# mixer-board2.net
KiCad netlist of a schematic drawn in EAGLE
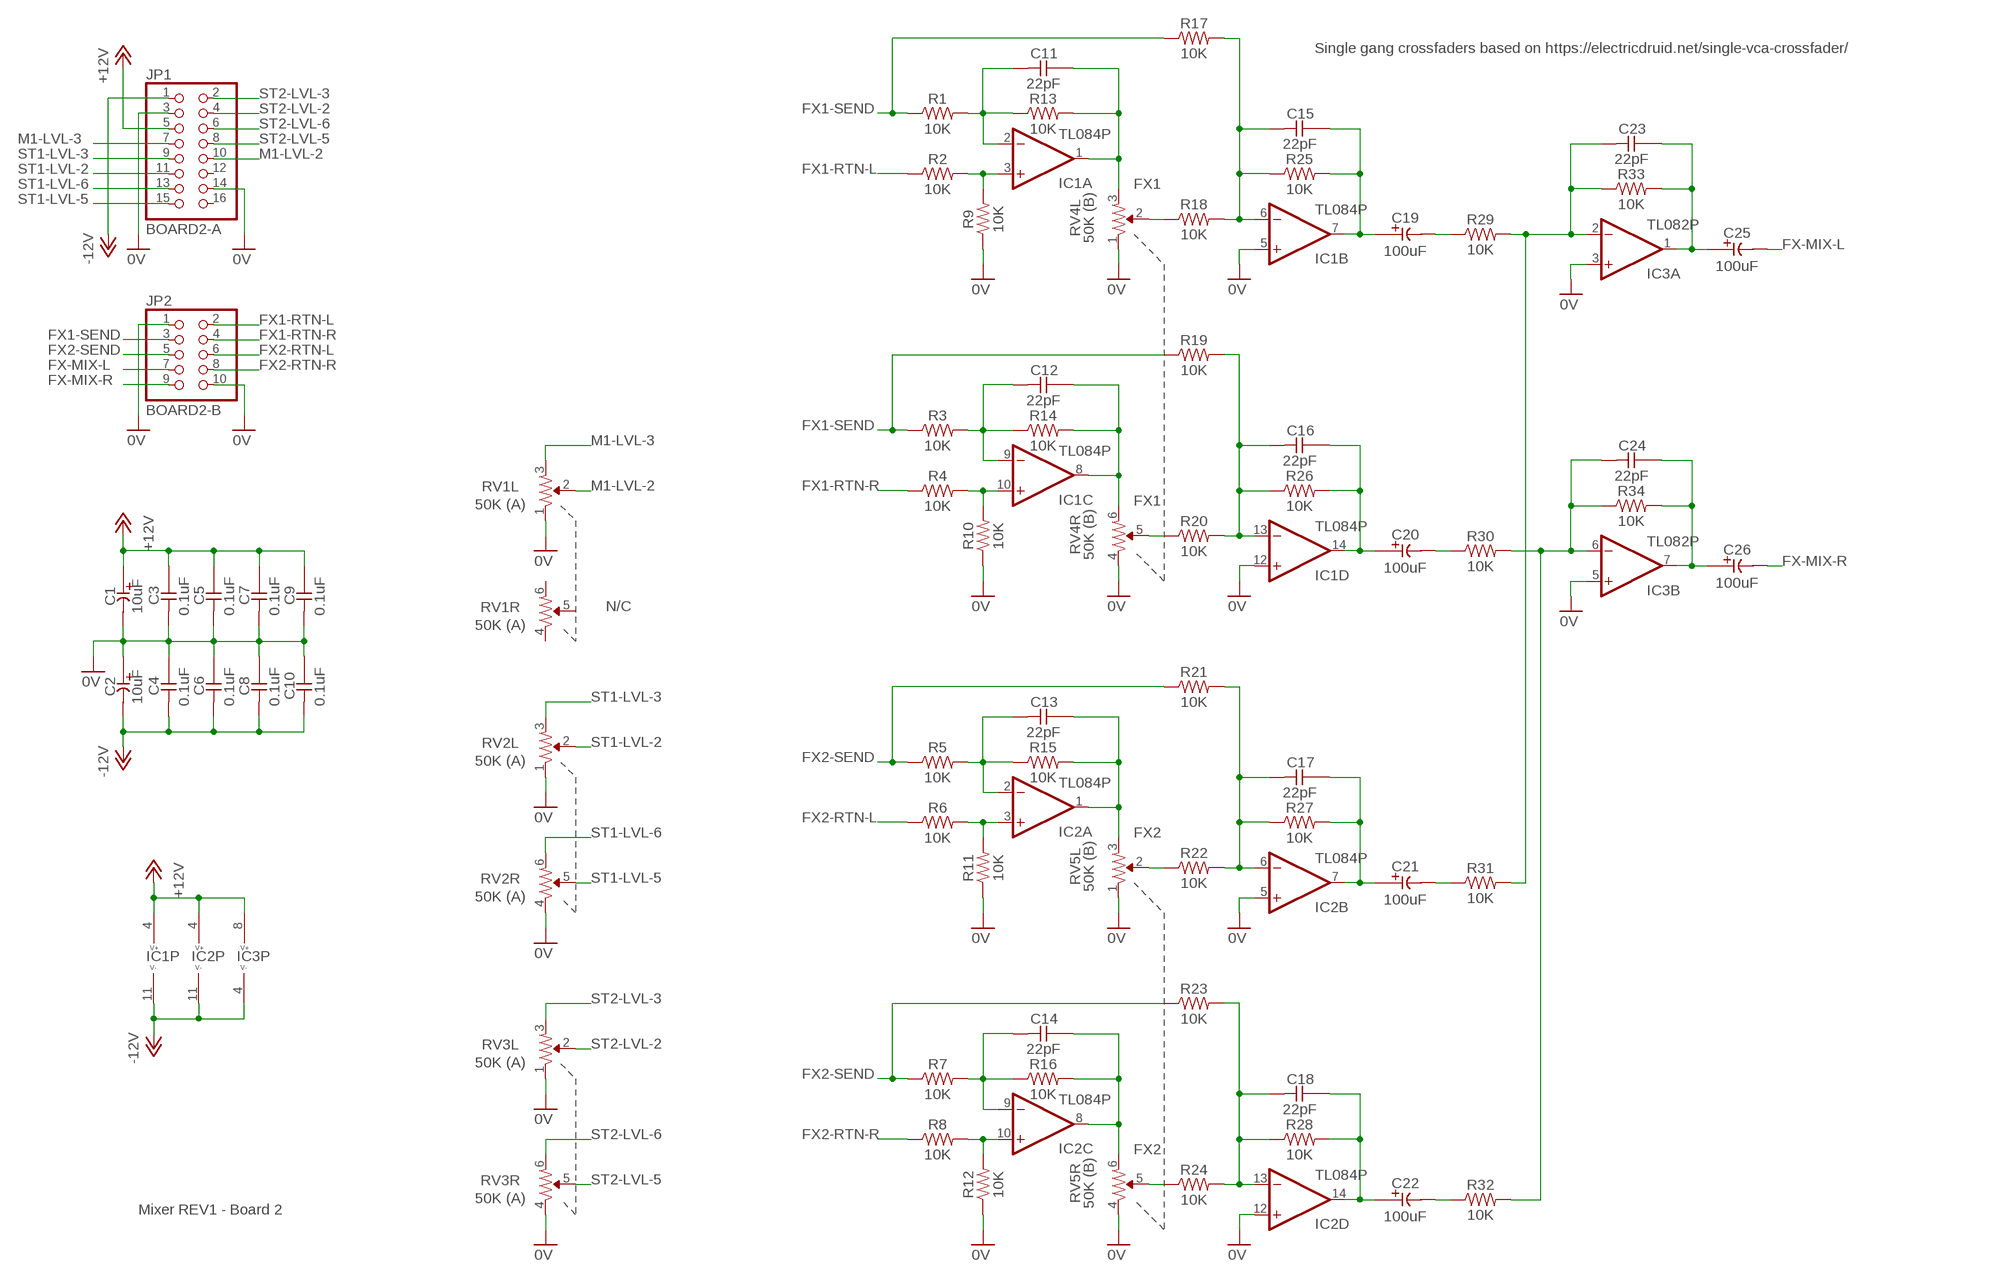
[diagram p0: schematic, sheet 1]

(export (version "E")
  (design (tool "Eeschema 10.0.6"))
  (components
    (comp (ref "C1")
      (value "10uF")
      (footprint "eagle-import:E2-5")
      (libsource (lib "eagle-import") (part "_common.v1_CE-USE2-5"))
    )
    (comp (ref "C2")
      (value "10uF")
      (footprint "eagle-import:E2-5")
      (libsource (lib "eagle-import") (part "_common.v1_CE-USE2-5"))
    )
    (comp (ref "C3")
      (value "0.1uF")
      (footprint "eagle-import:C025-024X044")
      (libsource (lib "eagle-import") (part "_common.v1_CC-US025-024X044"))
    )
    (comp (ref "C4")
      (value "0.1uF")
      (footprint "eagle-import:C025-024X044")
      (libsource (lib "eagle-import") (part "_common.v1_CC-US025-024X044"))
    )
    (comp (ref "C5")
      (value "0.1uF")
      (footprint "eagle-import:C025-024X044")
      (libsource (lib "eagle-import") (part "_common.v1_CC-US025-024X044"))
    )
    (comp (ref "C6")
      (value "0.1uF")
      (footprint "eagle-import:C025-024X044")
      (libsource (lib "eagle-import") (part "_common.v1_CC-US025-024X044"))
    )
    (comp (ref "C7")
      (value "0.1uF")
      (footprint "eagle-import:C025-024X044")
      (libsource (lib "eagle-import") (part "_common.v1_CC-US025-024X044"))
    )
    (comp (ref "C8")
      (value "0.1uF")
      (footprint "eagle-import:C025-024X044")
      (libsource (lib "eagle-import") (part "_common.v1_CC-US025-024X044"))
    )
    (comp (ref "C9")
      (value "0.1uF")
      (footprint "eagle-import:C025-024X044")
      (libsource (lib "eagle-import") (part "_common.v1_CC-US025-024X044"))
    )
    (comp (ref "C10")
      (value "0.1uF")
      (footprint "eagle-import:C025-024X044")
      (libsource (lib "eagle-import") (part "_common.v1_CC-US025-024X044"))
    )
    (comp (ref "C11")
      (value "22pF")
      (footprint "eagle-import:C025-024X044")
      (libsource (lib "eagle-import") (part "CC-US025-024X044"))
    )
    (comp (ref "C12")
      (value "22pF")
      (footprint "eagle-import:C025-024X044")
      (libsource (lib "eagle-import") (part "CC-US025-024X044"))
    )
    (comp (ref "C13")
      (value "22pF")
      (footprint "eagle-import:C025-024X044")
      (libsource (lib "eagle-import") (part "CC-US025-024X044"))
    )
    (comp (ref "C14")
      (value "22pF")
      (footprint "eagle-import:C025-024X044")
      (libsource (lib "eagle-import") (part "CC-US025-024X044"))
    )
    (comp (ref "C15")
      (value "22pF")
      (footprint "eagle-import:C025-024X044")
      (libsource (lib "eagle-import") (part "CC-US025-024X044"))
    )
    (comp (ref "C16")
      (value "22pF")
      (footprint "eagle-import:C025-024X044")
      (libsource (lib "eagle-import") (part "CC-US025-024X044"))
    )
    (comp (ref "C17")
      (value "22pF")
      (footprint "eagle-import:C025-024X044")
      (libsource (lib "eagle-import") (part "CC-US025-024X044"))
    )
    (comp (ref "C18")
      (value "22pF")
      (footprint "eagle-import:C025-024X044")
      (libsource (lib "eagle-import") (part "CC-US025-024X044"))
    )
    (comp (ref "C19")
      (value "100uF")
      (footprint "eagle-import:E5-8,5")
      (libsource (lib "eagle-import") (part "CE-USE5-8.5"))
    )
    (comp (ref "C20")
      (value "100uF")
      (footprint "eagle-import:E5-8,5")
      (libsource (lib "eagle-import") (part "CE-USE5-8.5"))
    )
    (comp (ref "C21")
      (value "100uF")
      (footprint "eagle-import:E5-8,5")
      (libsource (lib "eagle-import") (part "CE-USE5-8.5"))
    )
    (comp (ref "C22")
      (value "100uF")
      (footprint "eagle-import:E5-8,5")
      (libsource (lib "eagle-import") (part "CE-USE5-8.5"))
    )
    (comp (ref "C23")
      (value "22pF")
      (footprint "eagle-import:C025-024X044")
      (libsource (lib "eagle-import") (part "CC-US025-024X044"))
    )
    (comp (ref "C24")
      (value "22pF")
      (footprint "eagle-import:C025-024X044")
      (libsource (lib "eagle-import") (part "CC-US025-024X044"))
    )
    (comp (ref "C25")
      (value "100uF")
      (footprint "eagle-import:E5-8,5")
      (libsource (lib "eagle-import") (part "CE-USE5-8.5"))
    )
    (comp (ref "C26")
      (value "100uF")
      (footprint "eagle-import:E5-8,5")
      (libsource (lib "eagle-import") (part "CE-USE5-8.5"))
    )
    (comp (ref "IC1")
      (value "TL084P")
      (footprint "eagle-import:DIL14")
      (libsource (lib "eagle-import") (part "TL084P"))
    )
    (comp (ref "IC2")
      (value "TL084P")
      (footprint "eagle-import:DIL14")
      (libsource (lib "eagle-import") (part "TL084P"))
    )
    (comp (ref "IC3")
      (value "TL082P")
      (footprint "eagle-import:DIL08")
      (libsource (lib "eagle-import") (part "TL082P"))
    )
    (comp (ref "JP1")
      (value "BOARD2-A")
      (footprint "eagle-import:2X08")
      (libsource (lib "eagle-import") (part "PINHD-2X8"))
    )
    (comp (ref "JP2")
      (value "BOARD2-B")
      (footprint "eagle-import:2X05")
      (libsource (lib "eagle-import") (part "PINHD-2X5"))
    )
    (comp (ref "R1")
      (value "10K")
      (footprint "eagle-import:0207_7")
      (libsource (lib "eagle-import") (part "R"))
    )
    (comp (ref "R2")
      (value "10K")
      (footprint "eagle-import:0207_7")
      (libsource (lib "eagle-import") (part "R"))
    )
    (comp (ref "R3")
      (value "10K")
      (footprint "eagle-import:0207_7")
      (libsource (lib "eagle-import") (part "R"))
    )
    (comp (ref "R4")
      (value "10K")
      (footprint "eagle-import:0207_7")
      (libsource (lib "eagle-import") (part "R"))
    )
    (comp (ref "R5")
      (value "10K")
      (footprint "eagle-import:0207_7")
      (libsource (lib "eagle-import") (part "R"))
    )
    (comp (ref "R6")
      (value "10K")
      (footprint "eagle-import:0207_7")
      (libsource (lib "eagle-import") (part "R"))
    )
    (comp (ref "R7")
      (value "10K")
      (footprint "eagle-import:0207_7")
      (libsource (lib "eagle-import") (part "R"))
    )
    (comp (ref "R8")
      (value "10K")
      (footprint "eagle-import:0207_7")
      (libsource (lib "eagle-import") (part "R"))
    )
    (comp (ref "R9")
      (value "10K")
      (footprint "eagle-import:0207_7")
      (libsource (lib "eagle-import") (part "R"))
    )
    (comp (ref "R10")
      (value "10K")
      (footprint "eagle-import:0207_7")
      (libsource (lib "eagle-import") (part "R"))
    )
    (comp (ref "R11")
      (value "10K")
      (footprint "eagle-import:0207_7")
      (libsource (lib "eagle-import") (part "R"))
    )
    (comp (ref "R12")
      (value "10K")
      (footprint "eagle-import:0207_7")
      (libsource (lib "eagle-import") (part "R"))
    )
    (comp (ref "R13")
      (value "10K")
      (footprint "eagle-import:0207_7")
      (libsource (lib "eagle-import") (part "R"))
    )
    (comp (ref "R14")
      (value "10K")
      (footprint "eagle-import:0207_7")
      (libsource (lib "eagle-import") (part "R"))
    )
    (comp (ref "R15")
      (value "10K")
      (footprint "eagle-import:0207_7")
      (libsource (lib "eagle-import") (part "R"))
    )
    (comp (ref "R16")
      (value "10K")
      (footprint "eagle-import:0207_7")
      (libsource (lib "eagle-import") (part "R"))
    )
    (comp (ref "R17")
      (value "10K")
      (footprint "eagle-import:0207_7")
      (libsource (lib "eagle-import") (part "R"))
    )
    (comp (ref "R18")
      (value "10K")
      (footprint "eagle-import:0207_7")
      (libsource (lib "eagle-import") (part "R"))
    )
    (comp (ref "R19")
      (value "10K")
      (footprint "eagle-import:0207_7")
      (libsource (lib "eagle-import") (part "R"))
    )
    (comp (ref "R20")
      (value "10K")
      (footprint "eagle-import:0207_7")
      (libsource (lib "eagle-import") (part "R"))
    )
    (comp (ref "R21")
      (value "10K")
      (footprint "eagle-import:0207_7")
      (libsource (lib "eagle-import") (part "R"))
    )
    (comp (ref "R22")
      (value "10K")
      (footprint "eagle-import:0207_7")
      (libsource (lib "eagle-import") (part "R"))
    )
    (comp (ref "R23")
      (value "10K")
      (footprint "eagle-import:0207_7")
      (libsource (lib "eagle-import") (part "R"))
    )
    (comp (ref "R24")
      (value "10K")
      (footprint "eagle-import:0207_7")
      (libsource (lib "eagle-import") (part "R"))
    )
    (comp (ref "R25")
      (value "10K")
      (footprint "eagle-import:0207_7")
      (libsource (lib "eagle-import") (part "R"))
    )
    (comp (ref "R26")
      (value "10K")
      (footprint "eagle-import:0207_7")
      (libsource (lib "eagle-import") (part "R"))
    )
    (comp (ref "R27")
      (value "10K")
      (footprint "eagle-import:0207_7")
      (libsource (lib "eagle-import") (part "R"))
    )
    (comp (ref "R28")
      (value "10K")
      (footprint "eagle-import:0207_7")
      (libsource (lib "eagle-import") (part "R"))
    )
    (comp (ref "R29")
      (value "10K")
      (footprint "eagle-import:0207_7")
      (libsource (lib "eagle-import") (part "R"))
    )
    (comp (ref "R30")
      (value "10K")
      (footprint "eagle-import:0207_7")
      (libsource (lib "eagle-import") (part "R"))
    )
    (comp (ref "R31")
      (value "10K")
      (footprint "eagle-import:0207_7")
      (libsource (lib "eagle-import") (part "R"))
    )
    (comp (ref "R32")
      (value "10K")
      (footprint "eagle-import:0207_7")
      (libsource (lib "eagle-import") (part "R"))
    )
    (comp (ref "R33")
      (value "10K")
      (footprint "eagle-import:0207_7")
      (libsource (lib "eagle-import") (part "R"))
    )
    (comp (ref "R34")
      (value "10K")
      (footprint "eagle-import:0207_7")
      (libsource (lib "eagle-import") (part "R"))
    )
    (comp (ref "RV1")
      (value "50K (A)")
      (footprint "eagle-import:_COMMON_3RP_1610G")
      (libsource (lib "eagle-import") (part "R-VAR-ST"))
    )
    (comp (ref "RV2")
      (value "50K (A)")
      (footprint "eagle-import:_COMMON_3RP_1610G")
      (libsource (lib "eagle-import") (part "R-VAR-ST"))
    )
    (comp (ref "RV3")
      (value "50K (A)")
      (footprint "eagle-import:_COMMON_3RP_1610G")
      (libsource (lib "eagle-import") (part "R-VAR-ST"))
    )
    (comp (ref "RV4")
      (value "50K (B)")
      (footprint "eagle-import:_COMMON_3RP_1610G")
      (libsource (lib "eagle-import") (part "R-VAR-ST"))
    )
    (comp (ref "RV5")
      (value "50K (B)")
      (footprint "eagle-import:_COMMON_3RP_1610G")
      (libsource (lib "eagle-import") (part "R-VAR-ST"))
    )
  )
  (nets
    (net (code "1") (name "+12V") (class "Default")
      (node (ref "C1") (pin "+") (pinfunction "+_+") (pintype "passive"))
      (node (ref "C3") (pin "1") (pinfunction "1_1") (pintype "passive"))
      (node (ref "C5") (pin "1") (pinfunction "1_1") (pintype "passive"))
      (node (ref "C7") (pin "1") (pinfunction "1_1") (pintype "passive"))
      (node (ref "C9") (pin "1") (pinfunction "1_1") (pintype "passive"))
      (node (ref "IC1") (pin "4") (pinfunction "V+_4") (pintype "power_in"))
      (node (ref "IC2") (pin "4") (pinfunction "V+_4") (pintype "power_in"))
      (node (ref "IC3") (pin "8") (pinfunction "V+_8") (pintype "power_in"))
      (node (ref "JP1") (pin "5") (pinfunction "5_5") (pintype "passive"))
    )
    (net (code "2") (name "-12V") (class "Default")
      (node (ref "C10") (pin "2") (pinfunction "2_2") (pintype "passive"))
      (node (ref "C2") (pin "-") (pinfunction "-_-") (pintype "passive"))
      (node (ref "C4") (pin "2") (pinfunction "2_2") (pintype "passive"))
      (node (ref "C6") (pin "2") (pinfunction "2_2") (pintype "passive"))
      (node (ref "C8") (pin "2") (pinfunction "2_2") (pintype "passive"))
      (node (ref "IC1") (pin "11") (pinfunction "V-_11") (pintype "power_in"))
      (node (ref "IC2") (pin "11") (pinfunction "V-_11") (pintype "power_in"))
      (node (ref "IC3") (pin "4") (pinfunction "V-_4") (pintype "power_in"))
      (node (ref "JP1") (pin "1") (pinfunction "1_1") (pintype "passive"))
    )
    (net (code "3") (name "/FX-MIX-L") (class "Default")
      (node (ref "C25") (pin "-") (pinfunction "-_-") (pintype "passive"))
      (node (ref "JP2") (pin "7") (pinfunction "7_7") (pintype "passive"))
    )
    (net (code "4") (name "/FX-MIX-R") (class "Default")
      (node (ref "C26") (pin "-") (pinfunction "-_-") (pintype "passive"))
      (node (ref "JP2") (pin "9") (pinfunction "9_9") (pintype "passive"))
    )
    (net (code "5") (name "/FX1-RTN-L") (class "Default")
      (node (ref "JP2") (pin "2") (pinfunction "2_2") (pintype "passive"))
      (node (ref "R2") (pin "1") (pinfunction "1_1") (pintype "passive"))
    )
    (net (code "6") (name "/FX1-RTN-R") (class "Default")
      (node (ref "JP2") (pin "4") (pinfunction "4_4") (pintype "passive"))
      (node (ref "R4") (pin "1") (pinfunction "1_1") (pintype "passive"))
    )
    (net (code "7") (name "/FX1-SEND") (class "Default")
      (node (ref "JP2") (pin "3") (pinfunction "3_3") (pintype "passive"))
      (node (ref "R1") (pin "1") (pinfunction "1_1") (pintype "passive"))
      (node (ref "R17") (pin "1") (pinfunction "1_1") (pintype "passive"))
      (node (ref "R19") (pin "1") (pinfunction "1_1") (pintype "passive"))
      (node (ref "R3") (pin "1") (pinfunction "1_1") (pintype "passive"))
    )
    (net (code "8") (name "/FX2-RTN-L") (class "Default")
      (node (ref "JP2") (pin "6") (pinfunction "6_6") (pintype "passive"))
      (node (ref "R6") (pin "1") (pinfunction "1_1") (pintype "passive"))
    )
    (net (code "9") (name "/FX2-RTN-R") (class "Default")
      (node (ref "JP2") (pin "8") (pinfunction "8_8") (pintype "passive"))
      (node (ref "R8") (pin "1") (pinfunction "1_1") (pintype "passive"))
    )
    (net (code "10") (name "/FX2-SEND") (class "Default")
      (node (ref "JP2") (pin "5") (pinfunction "5_5") (pintype "passive"))
      (node (ref "R21") (pin "1") (pinfunction "1_1") (pintype "passive"))
      (node (ref "R23") (pin "1") (pinfunction "1_1") (pintype "passive"))
      (node (ref "R5") (pin "1") (pinfunction "1_1") (pintype "passive"))
      (node (ref "R7") (pin "1") (pinfunction "1_1") (pintype "passive"))
    )
    (net (code "11") (name "/M1-LVL-2") (class "Default")
      (node (ref "JP1") (pin "10") (pinfunction "10_10") (pintype "passive"))
      (node (ref "RV1") (pin "2") (pinfunction "2_2") (pintype "passive"))
    )
    (net (code "12") (name "/M1-LVL-3") (class "Default")
      (node (ref "JP1") (pin "7") (pinfunction "7_7") (pintype "passive"))
      (node (ref "RV1") (pin "3") (pinfunction "3_3") (pintype "passive"))
    )
    (net (code "13") (name "/ST1-LVL-2") (class "Default")
      (node (ref "JP1") (pin "11") (pinfunction "11_11") (pintype "passive"))
      (node (ref "RV2") (pin "2") (pinfunction "2_2") (pintype "passive"))
    )
    (net (code "14") (name "/ST1-LVL-3") (class "Default")
      (node (ref "JP1") (pin "9") (pinfunction "9_9") (pintype "passive"))
      (node (ref "RV2") (pin "3") (pinfunction "3_3") (pintype "passive"))
    )
    (net (code "15") (name "/ST1-LVL-5") (class "Default")
      (node (ref "JP1") (pin "15") (pinfunction "15_15") (pintype "passive"))
      (node (ref "RV2") (pin "5") (pinfunction "2_5") (pintype "passive"))
    )
    (net (code "16") (name "/ST1-LVL-6") (class "Default")
      (node (ref "JP1") (pin "13") (pinfunction "13_13") (pintype "passive"))
      (node (ref "RV2") (pin "6") (pinfunction "3_6") (pintype "passive"))
    )
    (net (code "17") (name "/ST2-LVL-2") (class "Default")
      (node (ref "JP1") (pin "4") (pinfunction "4_4") (pintype "passive"))
      (node (ref "RV3") (pin "2") (pinfunction "2_2") (pintype "passive"))
    )
    (net (code "18") (name "/ST2-LVL-3") (class "Default")
      (node (ref "JP1") (pin "2") (pinfunction "2_2") (pintype "passive"))
      (node (ref "RV3") (pin "3") (pinfunction "3_3") (pintype "passive"))
    )
    (net (code "19") (name "/ST2-LVL-5") (class "Default")
      (node (ref "JP1") (pin "8") (pinfunction "8_8") (pintype "passive"))
      (node (ref "RV3") (pin "5") (pinfunction "2_5") (pintype "passive"))
    )
    (net (code "20") (name "/ST2-LVL-6") (class "Default")
      (node (ref "JP1") (pin "6") (pinfunction "6_6") (pintype "passive"))
      (node (ref "RV3") (pin "6") (pinfunction "3_6") (pintype "passive"))
    )
    (net (code "21") (name "0V") (class "Default")
      (node (ref "C1") (pin "-") (pinfunction "-_-") (pintype "passive"))
      (node (ref "C10") (pin "1") (pinfunction "1_1") (pintype "passive"))
      (node (ref "C2") (pin "+") (pinfunction "+_+") (pintype "passive"))
      (node (ref "C3") (pin "2") (pinfunction "2_2") (pintype "passive"))
      (node (ref "C4") (pin "1") (pinfunction "1_1") (pintype "passive"))
      (node (ref "C5") (pin "2") (pinfunction "2_2") (pintype "passive"))
      (node (ref "C6") (pin "1") (pinfunction "1_1") (pintype "passive"))
      (node (ref "C7") (pin "2") (pinfunction "2_2") (pintype "passive"))
      (node (ref "C8") (pin "1") (pinfunction "1_1") (pintype "passive"))
      (node (ref "C9") (pin "2") (pinfunction "2_2") (pintype "passive"))
      (node (ref "IC1") (pin "12") (pinfunction "+IN_12") (pintype "input"))
      (node (ref "IC1") (pin "5") (pinfunction "+IN_5") (pintype "input"))
      (node (ref "IC2") (pin "12") (pinfunction "+IN_12") (pintype "input"))
      (node (ref "IC2") (pin "5") (pinfunction "+IN_5") (pintype "input"))
      (node (ref "IC3") (pin "3") (pinfunction "+IN_3") (pintype "input"))
      (node (ref "IC3") (pin "5") (pinfunction "+IN_5") (pintype "input"))
      (node (ref "JP1") (pin "14") (pinfunction "14_14") (pintype "passive"))
      (node (ref "JP1") (pin "3") (pinfunction "3_3") (pintype "passive"))
      (node (ref "JP2") (pin "1") (pinfunction "1_1") (pintype "passive"))
      (node (ref "JP2") (pin "10") (pinfunction "10_10") (pintype "passive"))
      (node (ref "R10") (pin "1") (pinfunction "1_1") (pintype "passive"))
      (node (ref "R11") (pin "1") (pinfunction "1_1") (pintype "passive"))
      (node (ref "R12") (pin "1") (pinfunction "1_1") (pintype "passive"))
      (node (ref "R9") (pin "1") (pinfunction "1_1") (pintype "passive"))
      (node (ref "RV1") (pin "1") (pinfunction "1_1") (pintype "passive"))
      (node (ref "RV2") (pin "1") (pinfunction "1_1") (pintype "passive"))
      (node (ref "RV2") (pin "4") (pinfunction "1_4") (pintype "passive"))
      (node (ref "RV3") (pin "1") (pinfunction "1_1") (pintype "passive"))
      (node (ref "RV3") (pin "4") (pinfunction "1_4") (pintype "passive"))
      (node (ref "RV4") (pin "1") (pinfunction "1_1") (pintype "passive"))
      (node (ref "RV4") (pin "4") (pinfunction "1_4") (pintype "passive"))
      (node (ref "RV5") (pin "1") (pinfunction "1_1") (pintype "passive"))
      (node (ref "RV5") (pin "4") (pinfunction "1_4") (pintype "passive"))
    )
    (net (code "22") (name "Net-(C19-Pad-)") (class "Default")
      (node (ref "C19") (pin "-") (pinfunction "-_-") (pintype "passive"))
      (node (ref "R29") (pin "1") (pinfunction "1_1") (pintype "passive"))
    )
    (net (code "23") (name "Net-(C20-Pad-)") (class "Default")
      (node (ref "C20") (pin "-") (pinfunction "-_-") (pintype "passive"))
      (node (ref "R30") (pin "1") (pinfunction "1_1") (pintype "passive"))
    )
    (net (code "24") (name "Net-(C21-Pad-)") (class "Default")
      (node (ref "C21") (pin "-") (pinfunction "-_-") (pintype "passive"))
      (node (ref "R31") (pin "1") (pinfunction "1_1") (pintype "passive"))
    )
    (net (code "25") (name "Net-(C22-Pad-)") (class "Default")
      (node (ref "C22") (pin "-") (pinfunction "-_-") (pintype "passive"))
      (node (ref "R32") (pin "1") (pinfunction "1_1") (pintype "passive"))
    )
    (net (code "26") (name "Net-(IC1A-+IN)") (class "Default")
      (node (ref "IC1") (pin "3") (pinfunction "+IN_3") (pintype "input"))
      (node (ref "R2") (pin "2") (pinfunction "2_2") (pintype "passive"))
      (node (ref "R9") (pin "2") (pinfunction "2_2") (pintype "passive"))
    )
    (net (code "27") (name "Net-(IC1A--IN)") (class "Default")
      (node (ref "C11") (pin "2") (pinfunction "2_2") (pintype "passive"))
      (node (ref "IC1") (pin "2") (pinfunction "-IN_2") (pintype "input"))
      (node (ref "R1") (pin "2") (pinfunction "2_2") (pintype "passive"))
      (node (ref "R13") (pin "1") (pinfunction "1_1") (pintype "passive"))
    )
    (net (code "28") (name "Net-(IC1A-OUT)") (class "Default")
      (node (ref "C11") (pin "1") (pinfunction "1_1") (pintype "passive"))
      (node (ref "IC1") (pin "1") (pinfunction "OUT_1") (pintype "output"))
      (node (ref "R13") (pin "2") (pinfunction "2_2") (pintype "passive"))
      (node (ref "RV4") (pin "3") (pinfunction "3_3") (pintype "passive"))
    )
    (net (code "29") (name "Net-(IC1B--IN)") (class "Default")
      (node (ref "C15") (pin "2") (pinfunction "2_2") (pintype "passive"))
      (node (ref "IC1") (pin "6") (pinfunction "-IN_6") (pintype "input"))
      (node (ref "R17") (pin "2") (pinfunction "2_2") (pintype "passive"))
      (node (ref "R18") (pin "2") (pinfunction "2_2") (pintype "passive"))
      (node (ref "R25") (pin "1") (pinfunction "1_1") (pintype "passive"))
    )
    (net (code "30") (name "Net-(IC1B-OUT)") (class "Default")
      (node (ref "C15") (pin "1") (pinfunction "1_1") (pintype "passive"))
      (node (ref "C19") (pin "+") (pinfunction "+_+") (pintype "passive"))
      (node (ref "IC1") (pin "7") (pinfunction "OUT_7") (pintype "output"))
      (node (ref "R25") (pin "2") (pinfunction "2_2") (pintype "passive"))
    )
    (net (code "31") (name "Net-(IC1C-+IN)") (class "Default")
      (node (ref "IC1") (pin "10") (pinfunction "+IN_10") (pintype "input"))
      (node (ref "R10") (pin "2") (pinfunction "2_2") (pintype "passive"))
      (node (ref "R4") (pin "2") (pinfunction "2_2") (pintype "passive"))
    )
    (net (code "32") (name "Net-(IC1C--IN)") (class "Default")
      (node (ref "C12") (pin "2") (pinfunction "2_2") (pintype "passive"))
      (node (ref "IC1") (pin "9") (pinfunction "-IN_9") (pintype "input"))
      (node (ref "R14") (pin "1") (pinfunction "1_1") (pintype "passive"))
      (node (ref "R3") (pin "2") (pinfunction "2_2") (pintype "passive"))
    )
    (net (code "33") (name "Net-(IC1C-OUT)") (class "Default")
      (node (ref "C12") (pin "1") (pinfunction "1_1") (pintype "passive"))
      (node (ref "IC1") (pin "8") (pinfunction "OUT_8") (pintype "output"))
      (node (ref "R14") (pin "2") (pinfunction "2_2") (pintype "passive"))
      (node (ref "RV4") (pin "6") (pinfunction "3_6") (pintype "passive"))
    )
    (net (code "34") (name "Net-(IC1D--IN)") (class "Default")
      (node (ref "C16") (pin "2") (pinfunction "2_2") (pintype "passive"))
      (node (ref "IC1") (pin "13") (pinfunction "-IN_13") (pintype "input"))
      (node (ref "R19") (pin "2") (pinfunction "2_2") (pintype "passive"))
      (node (ref "R20") (pin "2") (pinfunction "2_2") (pintype "passive"))
      (node (ref "R26") (pin "1") (pinfunction "1_1") (pintype "passive"))
    )
    (net (code "35") (name "Net-(IC1D-OUT)") (class "Default")
      (node (ref "C16") (pin "1") (pinfunction "1_1") (pintype "passive"))
      (node (ref "C20") (pin "+") (pinfunction "+_+") (pintype "passive"))
      (node (ref "IC1") (pin "14") (pinfunction "OUT_14") (pintype "output"))
      (node (ref "R26") (pin "2") (pinfunction "2_2") (pintype "passive"))
    )
    (net (code "36") (name "Net-(IC2A-+IN)") (class "Default")
      (node (ref "IC2") (pin "3") (pinfunction "+IN_3") (pintype "input"))
      (node (ref "R11") (pin "2") (pinfunction "2_2") (pintype "passive"))
      (node (ref "R6") (pin "2") (pinfunction "2_2") (pintype "passive"))
    )
    (net (code "37") (name "Net-(IC2A--IN)") (class "Default")
      (node (ref "C13") (pin "2") (pinfunction "2_2") (pintype "passive"))
      (node (ref "IC2") (pin "2") (pinfunction "-IN_2") (pintype "input"))
      (node (ref "R15") (pin "1") (pinfunction "1_1") (pintype "passive"))
      (node (ref "R5") (pin "2") (pinfunction "2_2") (pintype "passive"))
    )
    (net (code "38") (name "Net-(IC2A-OUT)") (class "Default")
      (node (ref "C13") (pin "1") (pinfunction "1_1") (pintype "passive"))
      (node (ref "IC2") (pin "1") (pinfunction "OUT_1") (pintype "output"))
      (node (ref "R15") (pin "2") (pinfunction "2_2") (pintype "passive"))
      (node (ref "RV5") (pin "3") (pinfunction "3_3") (pintype "passive"))
    )
    (net (code "39") (name "Net-(IC2B--IN)") (class "Default")
      (node (ref "C17") (pin "2") (pinfunction "2_2") (pintype "passive"))
      (node (ref "IC2") (pin "6") (pinfunction "-IN_6") (pintype "input"))
      (node (ref "R21") (pin "2") (pinfunction "2_2") (pintype "passive"))
      (node (ref "R22") (pin "2") (pinfunction "2_2") (pintype "passive"))
      (node (ref "R27") (pin "1") (pinfunction "1_1") (pintype "passive"))
    )
    (net (code "40") (name "Net-(IC2B-OUT)") (class "Default")
      (node (ref "C17") (pin "1") (pinfunction "1_1") (pintype "passive"))
      (node (ref "C21") (pin "+") (pinfunction "+_+") (pintype "passive"))
      (node (ref "IC2") (pin "7") (pinfunction "OUT_7") (pintype "output"))
      (node (ref "R27") (pin "2") (pinfunction "2_2") (pintype "passive"))
    )
    (net (code "41") (name "Net-(IC2C-+IN)") (class "Default")
      (node (ref "IC2") (pin "10") (pinfunction "+IN_10") (pintype "input"))
      (node (ref "R12") (pin "2") (pinfunction "2_2") (pintype "passive"))
      (node (ref "R8") (pin "2") (pinfunction "2_2") (pintype "passive"))
    )
    (net (code "42") (name "Net-(IC2C--IN)") (class "Default")
      (node (ref "C14") (pin "2") (pinfunction "2_2") (pintype "passive"))
      (node (ref "IC2") (pin "9") (pinfunction "-IN_9") (pintype "input"))
      (node (ref "R16") (pin "1") (pinfunction "1_1") (pintype "passive"))
      (node (ref "R7") (pin "2") (pinfunction "2_2") (pintype "passive"))
    )
    (net (code "43") (name "Net-(IC2C-OUT)") (class "Default")
      (node (ref "C14") (pin "1") (pinfunction "1_1") (pintype "passive"))
      (node (ref "IC2") (pin "8") (pinfunction "OUT_8") (pintype "output"))
      (node (ref "R16") (pin "2") (pinfunction "2_2") (pintype "passive"))
      (node (ref "RV5") (pin "6") (pinfunction "3_6") (pintype "passive"))
    )
    (net (code "44") (name "Net-(IC2D--IN)") (class "Default")
      (node (ref "C18") (pin "2") (pinfunction "2_2") (pintype "passive"))
      (node (ref "IC2") (pin "13") (pinfunction "-IN_13") (pintype "input"))
      (node (ref "R23") (pin "2") (pinfunction "2_2") (pintype "passive"))
      (node (ref "R24") (pin "2") (pinfunction "2_2") (pintype "passive"))
      (node (ref "R28") (pin "1") (pinfunction "1_1") (pintype "passive"))
    )
    (net (code "45") (name "Net-(IC2D-OUT)") (class "Default")
      (node (ref "C18") (pin "1") (pinfunction "1_1") (pintype "passive"))
      (node (ref "C22") (pin "+") (pinfunction "+_+") (pintype "passive"))
      (node (ref "IC2") (pin "14") (pinfunction "OUT_14") (pintype "output"))
      (node (ref "R28") (pin "2") (pinfunction "2_2") (pintype "passive"))
    )
    (net (code "46") (name "Net-(IC3A--IN)") (class "Default")
      (node (ref "C23") (pin "2") (pinfunction "2_2") (pintype "passive"))
      (node (ref "IC3") (pin "2") (pinfunction "-IN_2") (pintype "input"))
      (node (ref "R29") (pin "2") (pinfunction "2_2") (pintype "passive"))
      (node (ref "R31") (pin "2") (pinfunction "2_2") (pintype "passive"))
      (node (ref "R33") (pin "1") (pinfunction "1_1") (pintype "passive"))
    )
    (net (code "47") (name "Net-(IC3A-OUT)") (class "Default")
      (node (ref "C23") (pin "1") (pinfunction "1_1") (pintype "passive"))
      (node (ref "C25") (pin "+") (pinfunction "+_+") (pintype "passive"))
      (node (ref "IC3") (pin "1") (pinfunction "OUT_1") (pintype "output"))
      (node (ref "R33") (pin "2") (pinfunction "2_2") (pintype "passive"))
    )
    (net (code "48") (name "Net-(IC3B--IN)") (class "Default")
      (node (ref "C24") (pin "2") (pinfunction "2_2") (pintype "passive"))
      (node (ref "IC3") (pin "6") (pinfunction "-IN_6") (pintype "input"))
      (node (ref "R30") (pin "2") (pinfunction "2_2") (pintype "passive"))
      (node (ref "R32") (pin "2") (pinfunction "2_2") (pintype "passive"))
      (node (ref "R34") (pin "1") (pinfunction "1_1") (pintype "passive"))
    )
    (net (code "49") (name "Net-(IC3B-OUT)") (class "Default")
      (node (ref "C24") (pin "1") (pinfunction "1_1") (pintype "passive"))
      (node (ref "C26") (pin "+") (pinfunction "+_+") (pintype "passive"))
      (node (ref "IC3") (pin "7") (pinfunction "OUT_7") (pintype "output"))
      (node (ref "R34") (pin "2") (pinfunction "2_2") (pintype "passive"))
    )
    (net (code "50") (name "Net-(R18-Pad1)") (class "Default")
      (node (ref "R18") (pin "1") (pinfunction "1_1") (pintype "passive"))
      (node (ref "RV4") (pin "2") (pinfunction "2_2") (pintype "passive"))
    )
    (net (code "51") (name "Net-(R22-Pad1)") (class "Default")
      (node (ref "R22") (pin "1") (pinfunction "1_1") (pintype "passive"))
      (node (ref "RV5") (pin "2") (pinfunction "2_2") (pintype "passive"))
    )
    (net (code "52") (name "Net-(RV4B-2)") (class "Default")
      (node (ref "R20") (pin "1") (pinfunction "1_1") (pintype "passive"))
      (node (ref "RV4") (pin "5") (pinfunction "2_5") (pintype "passive"))
    )
    (net (code "53") (name "Net-(RV5B-2)") (class "Default")
      (node (ref "R24") (pin "1") (pinfunction "1_1") (pintype "passive"))
      (node (ref "RV5") (pin "5") (pinfunction "2_5") (pintype "passive"))
    )
    (net (code "54") (name "unconnected-(JP1-Pad12)") (class "Default")
      (node (ref "JP1") (pin "12") (pinfunction "12_12") (pintype "passive"))
    )
    (net (code "55") (name "unconnected-(JP1-Pad16)") (class "Default")
      (node (ref "JP1") (pin "16") (pinfunction "16_16") (pintype "passive"))
    )
    (net (code "56") (name "unconnected-(RV1B-1-Pad4)") (class "Default")
      (node (ref "RV1") (pin "4") (pinfunction "1_4") (pintype "passive"))
    )
    (net (code "57") (name "unconnected-(RV1B-2-Pad5)") (class "Default")
      (node (ref "RV1") (pin "5") (pinfunction "2_5") (pintype "passive"))
    )
    (net (code "58") (name "unconnected-(RV1B-3-Pad6)") (class "Default")
      (node (ref "RV1") (pin "6") (pinfunction "3_6") (pintype "passive"))
    )
  )
)
